# ProgrammateurFilPilote_1_1_1.net
KiCad netlist of a schematic drawn in EAGLE
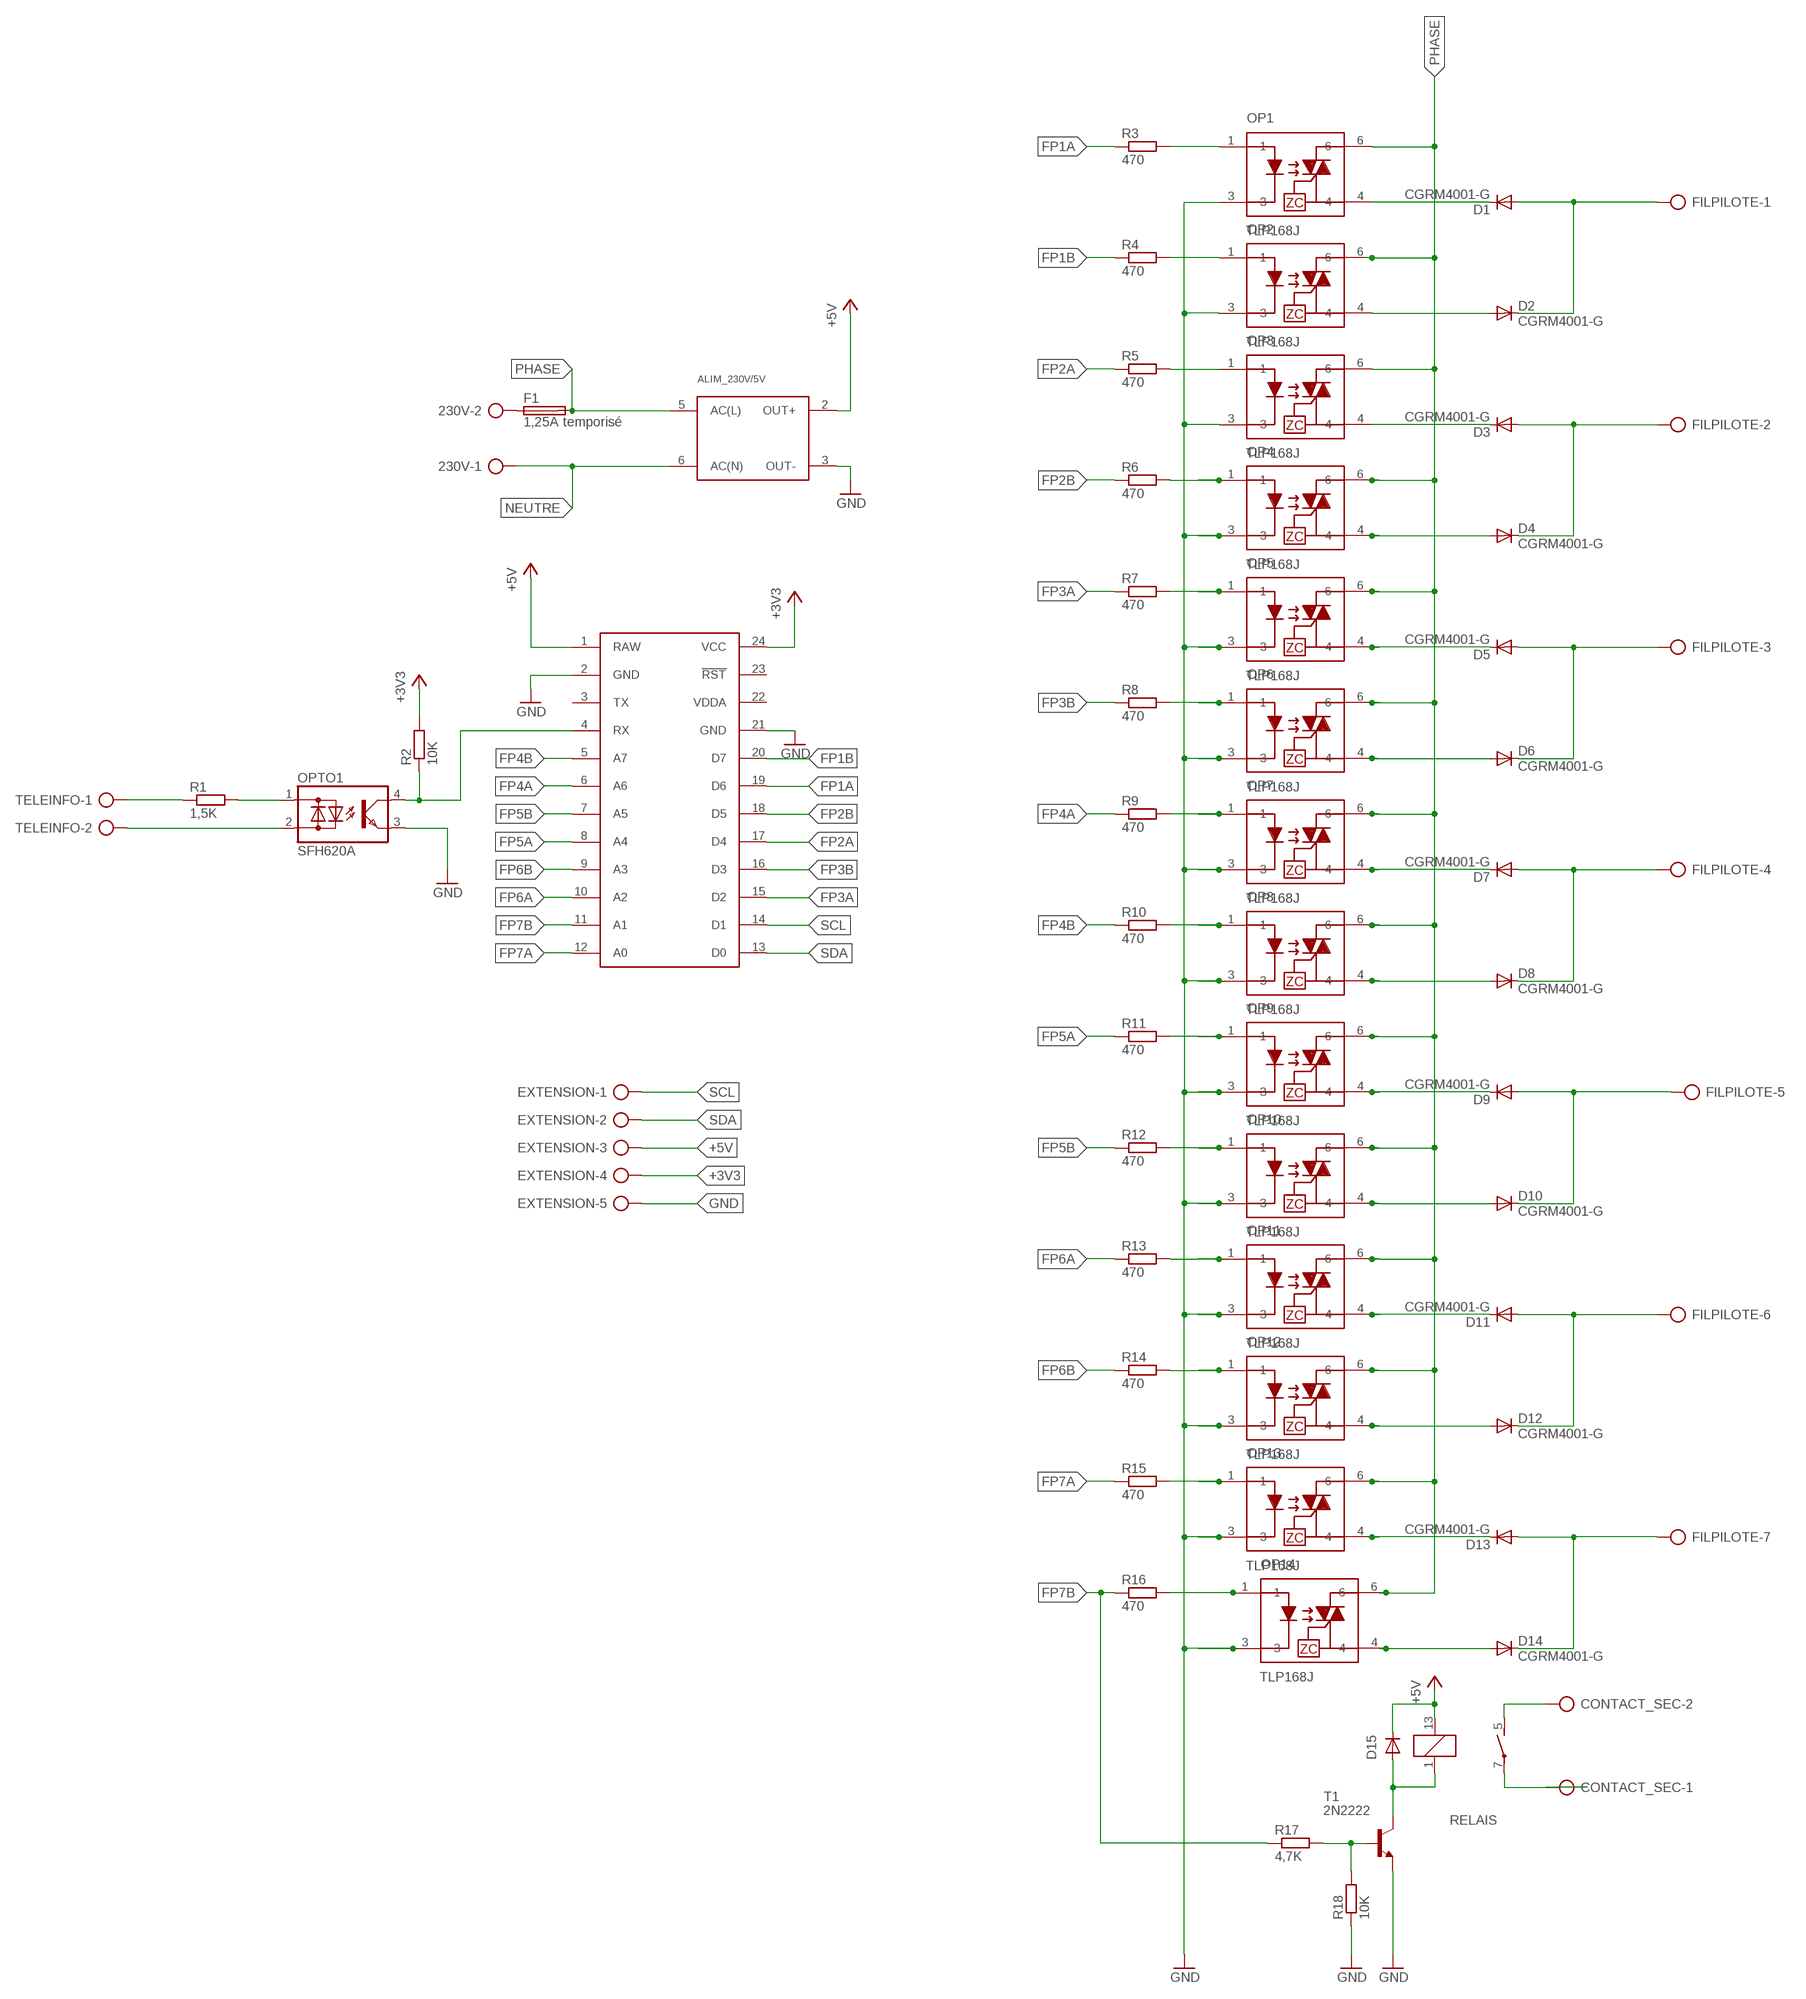
[diagram p0: schematic, sheet 1]

(export (version "E")
  (design (tool "Eeschema 10.0.6"))
  (components
    (comp (ref "230V")
      (value "AK500/2")
      (footprint "eagle-import:AK500_2")
      (libsource (lib "eagle-import") (part "AK500/2"))
    )
    (comp (ref "ALIM_230V/5V")
      (value "TMLM04-SINGLE")
      (footprint "eagle-import:TMLM04")
      (libsource (lib "eagle-import") (part "TMLM04-SINGLE"))
    )
    (comp (ref "CONTACT_SEC")
      (value "AK500/2")
      (footprint "eagle-import:AK500_2")
      (libsource (lib "eagle-import") (part "AK500/2"))
    )
    (comp (ref "D1")
      (value "CGRM4001-G")
      (footprint "eagle-import:SOD-123_MINI-SMA")
      (libsource (lib "eagle-import") (part "CGRM400-G1"))
    )
    (comp (ref "D2")
      (value "CGRM4001-G")
      (footprint "eagle-import:SOD-123_MINI-SMA")
      (libsource (lib "eagle-import") (part "CGRM400-G1"))
    )
    (comp (ref "D3")
      (value "CGRM4001-G")
      (footprint "eagle-import:SOD-123_MINI-SMA")
      (libsource (lib "eagle-import") (part "CGRM400-G1"))
    )
    (comp (ref "D4")
      (value "CGRM4001-G")
      (footprint "eagle-import:SOD-123_MINI-SMA")
      (libsource (lib "eagle-import") (part "CGRM400-G1"))
    )
    (comp (ref "D5")
      (value "CGRM4001-G")
      (footprint "eagle-import:SOD-123_MINI-SMA")
      (libsource (lib "eagle-import") (part "CGRM400-G1"))
    )
    (comp (ref "D6")
      (value "CGRM4001-G")
      (footprint "eagle-import:SOD-123_MINI-SMA")
      (libsource (lib "eagle-import") (part "CGRM400-G1"))
    )
    (comp (ref "D7")
      (value "CGRM4001-G")
      (footprint "eagle-import:SOD-123_MINI-SMA")
      (libsource (lib "eagle-import") (part "CGRM400-G1"))
    )
    (comp (ref "D8")
      (value "CGRM4001-G")
      (footprint "eagle-import:SOD-123_MINI-SMA")
      (libsource (lib "eagle-import") (part "CGRM400-G1"))
    )
    (comp (ref "D9")
      (value "CGRM4001-G")
      (footprint "eagle-import:SOD-123_MINI-SMA")
      (libsource (lib "eagle-import") (part "CGRM400-G1"))
    )
    (comp (ref "D10")
      (value "CGRM4001-G")
      (footprint "eagle-import:SOD-123_MINI-SMA")
      (libsource (lib "eagle-import") (part "CGRM400-G1"))
    )
    (comp (ref "D11")
      (value "CGRM4001-G")
      (footprint "eagle-import:SOD-123_MINI-SMA")
      (libsource (lib "eagle-import") (part "CGRM400-G1"))
    )
    (comp (ref "D12")
      (value "CGRM4001-G")
      (footprint "eagle-import:SOD-123_MINI-SMA")
      (libsource (lib "eagle-import") (part "CGRM400-G1"))
    )
    (comp (ref "D13")
      (value "CGRM4001-G")
      (footprint "eagle-import:SOD-123_MINI-SMA")
      (libsource (lib "eagle-import") (part "CGRM400-G1"))
    )
    (comp (ref "D14")
      (value "CGRM4001-G")
      (footprint "eagle-import:SOD-123_MINI-SMA")
      (libsource (lib "eagle-import") (part "CGRM400-G1"))
    )
    (comp (ref "D15")
      (value "CGRM4001-G")
      (footprint "eagle-import:SOD-123_MINI-SMA")
      (libsource (lib "eagle-import") (part "CGRM400-G1"))
    )
    (comp (ref "EXTENSION")
      (value "AK500/5")
      (footprint "eagle-import:AK500_5")
      (libsource (lib "eagle-import") (part "AK500/5"))
    )
    (comp (ref "F1")
      (value "1,25A temporisé")
      (footprint "eagle-import:TE5")
      (libsource (lib "eagle-import") (part "TE5"))
    )
    (comp (ref "FILPILOTE")
      (value "AK500/7")
      (footprint "eagle-import:AK500_7")
      (libsource (lib "eagle-import") (part "AK500/7"))
    )
    (comp (ref "OP1")
      (value "TLP168J")
      (footprint "eagle-import:MFSOP-4")
      (libsource (lib "eagle-import") (part "TLP168J"))
    )
    (comp (ref "OP2")
      (value "TLP168J")
      (footprint "eagle-import:MFSOP-4")
      (libsource (lib "eagle-import") (part "TLP168J"))
    )
    (comp (ref "OP3")
      (value "TLP168J")
      (footprint "eagle-import:MFSOP-4")
      (libsource (lib "eagle-import") (part "TLP168J"))
    )
    (comp (ref "OP4")
      (value "TLP168J")
      (footprint "eagle-import:MFSOP-4")
      (libsource (lib "eagle-import") (part "TLP168J"))
    )
    (comp (ref "OP5")
      (value "TLP168J")
      (footprint "eagle-import:MFSOP-4")
      (libsource (lib "eagle-import") (part "TLP168J"))
    )
    (comp (ref "OP6")
      (value "TLP168J")
      (footprint "eagle-import:MFSOP-4")
      (libsource (lib "eagle-import") (part "TLP168J"))
    )
    (comp (ref "OP7")
      (value "TLP168J")
      (footprint "eagle-import:MFSOP-4")
      (libsource (lib "eagle-import") (part "TLP168J"))
    )
    (comp (ref "OP8")
      (value "TLP168J")
      (footprint "eagle-import:MFSOP-4")
      (libsource (lib "eagle-import") (part "TLP168J"))
    )
    (comp (ref "OP9")
      (value "TLP168J")
      (footprint "eagle-import:MFSOP-4")
      (libsource (lib "eagle-import") (part "TLP168J"))
    )
    (comp (ref "OP10")
      (value "TLP168J")
      (footprint "eagle-import:MFSOP-4")
      (libsource (lib "eagle-import") (part "TLP168J"))
    )
    (comp (ref "OP11")
      (value "TLP168J")
      (footprint "eagle-import:MFSOP-4")
      (libsource (lib "eagle-import") (part "TLP168J"))
    )
    (comp (ref "OP12")
      (value "TLP168J")
      (footprint "eagle-import:MFSOP-4")
      (libsource (lib "eagle-import") (part "TLP168J"))
    )
    (comp (ref "OP13")
      (value "TLP168J")
      (footprint "eagle-import:MFSOP-4")
      (libsource (lib "eagle-import") (part "TLP168J"))
    )
    (comp (ref "OP14")
      (value "TLP168J")
      (footprint "eagle-import:MFSOP-4")
      (libsource (lib "eagle-import") (part "TLP168J"))
    )
    (comp (ref "OPTO1")
      (value "SFH620A")
      (footprint "eagle-import:DIL04")
      (fields (field (name "MPN") "SFH620A-2"))
      (libsource (lib "eagle-import") (part "SFH620A"))
    )
    (comp (ref "R1")
      (value "1,5K")
      (footprint "eagle-import:R1206")
      (libsource (lib "eagle-import") (part "R-EU_R1206"))
    )
    (comp (ref "R2")
      (value "10K")
      (footprint "eagle-import:R1206")
      (libsource (lib "eagle-import") (part "R-EU_R1206"))
    )
    (comp (ref "R3")
      (value "470")
      (footprint "eagle-import:R1206")
      (libsource (lib "eagle-import") (part "R-EU_R1206"))
    )
    (comp (ref "R4")
      (value "470")
      (footprint "eagle-import:R1206")
      (libsource (lib "eagle-import") (part "R-EU_R1206"))
    )
    (comp (ref "R5")
      (value "470")
      (footprint "eagle-import:R1206")
      (libsource (lib "eagle-import") (part "R-EU_R1206"))
    )
    (comp (ref "R6")
      (value "470")
      (footprint "eagle-import:R1206")
      (libsource (lib "eagle-import") (part "R-EU_R1206"))
    )
    (comp (ref "R7")
      (value "470")
      (footprint "eagle-import:R1206")
      (libsource (lib "eagle-import") (part "R-EU_R1206"))
    )
    (comp (ref "R8")
      (value "470")
      (footprint "eagle-import:R1206")
      (libsource (lib "eagle-import") (part "R-EU_R1206"))
    )
    (comp (ref "R9")
      (value "470")
      (footprint "eagle-import:R1206")
      (libsource (lib "eagle-import") (part "R-EU_R1206"))
    )
    (comp (ref "R10")
      (value "470")
      (footprint "eagle-import:R1206")
      (libsource (lib "eagle-import") (part "R-EU_R1206"))
    )
    (comp (ref "R11")
      (value "470")
      (footprint "eagle-import:R1206")
      (libsource (lib "eagle-import") (part "R-EU_R1206"))
    )
    (comp (ref "R12")
      (value "470")
      (footprint "eagle-import:R1206")
      (libsource (lib "eagle-import") (part "R-EU_R1206"))
    )
    (comp (ref "R13")
      (value "470")
      (footprint "eagle-import:R1206")
      (libsource (lib "eagle-import") (part "R-EU_R1206"))
    )
    (comp (ref "R14")
      (value "470")
      (footprint "eagle-import:R1206")
      (libsource (lib "eagle-import") (part "R-EU_R1206"))
    )
    (comp (ref "R15")
      (value "470")
      (footprint "eagle-import:R1206")
      (libsource (lib "eagle-import") (part "R-EU_R1206"))
    )
    (comp (ref "R16")
      (value "470")
      (footprint "eagle-import:R1206")
      (libsource (lib "eagle-import") (part "R-EU_R1206"))
    )
    (comp (ref "R17")
      (value "4,7K")
      (footprint "eagle-import:R1206")
      (libsource (lib "eagle-import") (part "R-EU_R1206"))
    )
    (comp (ref "R18")
      (value "10K")
      (footprint "eagle-import:R1206")
      (libsource (lib "eagle-import") (part "R-EU_R1206"))
    )
    (comp (ref "RELAIS")
      (value "Relais G6D")
      (footprint "eagle-import:G6D")
      (libsource (lib "eagle-import") (part "G6D?-1A-ASI12VDC"))
    )
    (comp (ref "SPARKCORE")
      (value "SPARK_CORECORE")
      (footprint "eagle-import:SPARK_CORE")
      (libsource (lib "eagle-import") (part "SPARK_CORECORE"))
    )
    (comp (ref "T1")
      (value "2N2222")
      (footprint "eagle-import:TO92-EBC")
      (libsource (lib "eagle-import") (part "-NPN-TO92-EBC2N2222"))
    )
    (comp (ref "TELEINFO")
      (value "AK500/2")
      (footprint "eagle-import:AK500_2")
      (libsource (lib "eagle-import") (part "AK500/2"))
    )
  )
  (nets
    (net (code "1") (name "+3V3") (class "Default")
      (node (ref "EXTENSION") (pin "4") (pinfunction "KL_4") (pintype "passive"))
      (node (ref "R2") (pin "2") (pinfunction "2_2") (pintype "passive"))
      (node (ref "SPARKCORE") (pin "24") (pinfunction "VCC_24") (pintype "power_in"))
    )
    (net (code "2") (name "+5V") (class "Default")
      (node (ref "ALIM_230V/5V") (pin "2") (pinfunction "OUT+_2") (pintype "passive"))
      (node (ref "D15") (pin "C") (pinfunction "C_C") (pintype "passive"))
      (node (ref "EXTENSION") (pin "3") (pinfunction "KL_3") (pintype "passive"))
      (node (ref "RELAIS") (pin "13") (pinfunction "2_13") (pintype "passive"))
      (node (ref "SPARKCORE") (pin "1") (pinfunction "RAW_1") (pintype "power_in"))
    )
    (net (code "3") (name "/VDDA") (class "Default")
      (node (ref "SPARKCORE") (pin "22") (pinfunction "VDDA_22") (pintype "power_in"))
    )
    (net (code "4") (name "FP1A") (class "Default")
      (node (ref "R3") (pin "1") (pinfunction "1_1") (pintype "passive"))
      (node (ref "SPARKCORE") (pin "19") (pinfunction "D6_19") (pintype "bidirectional"))
    )
    (net (code "5") (name "FP1B") (class "Default")
      (node (ref "R4") (pin "1") (pinfunction "1_1") (pintype "passive"))
      (node (ref "SPARKCORE") (pin "20") (pinfunction "D7_20") (pintype "bidirectional"))
    )
    (net (code "6") (name "FP2A") (class "Default")
      (node (ref "R5") (pin "1") (pinfunction "1_1") (pintype "passive"))
      (node (ref "SPARKCORE") (pin "17") (pinfunction "D4_17") (pintype "bidirectional"))
    )
    (net (code "7") (name "FP2B") (class "Default")
      (node (ref "R6") (pin "1") (pinfunction "1_1") (pintype "passive"))
      (node (ref "SPARKCORE") (pin "18") (pinfunction "D5_18") (pintype "bidirectional"))
    )
    (net (code "8") (name "FP3A") (class "Default")
      (node (ref "R7") (pin "1") (pinfunction "1_1") (pintype "passive"))
      (node (ref "SPARKCORE") (pin "15") (pinfunction "D2_15") (pintype "bidirectional"))
    )
    (net (code "9") (name "FP3B") (class "Default")
      (node (ref "R8") (pin "1") (pinfunction "1_1") (pintype "passive"))
      (node (ref "SPARKCORE") (pin "16") (pinfunction "D3_16") (pintype "bidirectional"))
    )
    (net (code "10") (name "FP4A") (class "Default")
      (node (ref "R9") (pin "1") (pinfunction "1_1") (pintype "passive"))
      (node (ref "SPARKCORE") (pin "6") (pinfunction "A6_6") (pintype "bidirectional"))
    )
    (net (code "11") (name "FP4B") (class "Default")
      (node (ref "R10") (pin "1") (pinfunction "1_1") (pintype "passive"))
      (node (ref "SPARKCORE") (pin "5") (pinfunction "A7_5") (pintype "bidirectional"))
    )
    (net (code "12") (name "FP5A") (class "Default")
      (node (ref "R11") (pin "1") (pinfunction "1_1") (pintype "passive"))
      (node (ref "SPARKCORE") (pin "8") (pinfunction "A4_8") (pintype "bidirectional"))
    )
    (net (code "13") (name "FP5B") (class "Default")
      (node (ref "R12") (pin "1") (pinfunction "1_1") (pintype "passive"))
      (node (ref "SPARKCORE") (pin "7") (pinfunction "A5_7") (pintype "bidirectional"))
    )
    (net (code "14") (name "FP6A") (class "Default")
      (node (ref "R13") (pin "1") (pinfunction "1_1") (pintype "passive"))
      (node (ref "SPARKCORE") (pin "10") (pinfunction "A2_10") (pintype "bidirectional"))
    )
    (net (code "15") (name "FP6B") (class "Default")
      (node (ref "R14") (pin "1") (pinfunction "1_1") (pintype "passive"))
      (node (ref "SPARKCORE") (pin "9") (pinfunction "A3_9") (pintype "bidirectional"))
    )
    (net (code "16") (name "FP7A") (class "Default")
      (node (ref "R15") (pin "1") (pinfunction "1_1") (pintype "passive"))
      (node (ref "SPARKCORE") (pin "12") (pinfunction "A0_12") (pintype "bidirectional"))
    )
    (net (code "17") (name "FP7B") (class "Default")
      (node (ref "R16") (pin "1") (pinfunction "1_1") (pintype "passive"))
      (node (ref "R17") (pin "1") (pinfunction "1_1") (pintype "passive"))
      (node (ref "SPARKCORE") (pin "11") (pinfunction "A1_11") (pintype "bidirectional"))
    )
    (net (code "18") (name "GND") (class "Default")
      (node (ref "ALIM_230V/5V") (pin "3") (pinfunction "OUT-_3") (pintype "passive"))
      (node (ref "EXTENSION") (pin "5") (pinfunction "KL_5") (pintype "passive"))
      (node (ref "OP1") (pin "3") (pinfunction "3_3") (pintype "bidirectional"))
      (node (ref "OP10") (pin "3") (pinfunction "3_3") (pintype "bidirectional"))
      (node (ref "OP11") (pin "3") (pinfunction "3_3") (pintype "bidirectional"))
      (node (ref "OP12") (pin "3") (pinfunction "3_3") (pintype "bidirectional"))
      (node (ref "OP13") (pin "3") (pinfunction "3_3") (pintype "bidirectional"))
      (node (ref "OP14") (pin "3") (pinfunction "3_3") (pintype "bidirectional"))
      (node (ref "OP2") (pin "3") (pinfunction "3_3") (pintype "bidirectional"))
      (node (ref "OP3") (pin "3") (pinfunction "3_3") (pintype "bidirectional"))
      (node (ref "OP4") (pin "3") (pinfunction "3_3") (pintype "bidirectional"))
      (node (ref "OP5") (pin "3") (pinfunction "3_3") (pintype "bidirectional"))
      (node (ref "OP6") (pin "3") (pinfunction "3_3") (pintype "bidirectional"))
      (node (ref "OP7") (pin "3") (pinfunction "3_3") (pintype "bidirectional"))
      (node (ref "OP8") (pin "3") (pinfunction "3_3") (pintype "bidirectional"))
      (node (ref "OP9") (pin "3") (pinfunction "3_3") (pintype "bidirectional"))
      (node (ref "OPTO1") (pin "3") (pinfunction "E_3") (pintype "passive"))
      (node (ref "R18") (pin "1") (pinfunction "1_1") (pintype "passive"))
      (node (ref "SPARKCORE") (pin "2") (pinfunction "GND_2") (pintype "power_in"))
      (node (ref "SPARKCORE") (pin "21") (pinfunction "GND_21") (pintype "power_in"))
      (node (ref "T1") (pin "E") (pinfunction "E_E") (pintype "passive"))
    )
    (net (code "19") (name "NEUTRE") (class "Default")
      (node (ref "230V") (pin "1") (pinfunction "KL_1") (pintype "passive"))
      (node (ref "ALIM_230V/5V") (pin "6") (pinfunction "AC(N)_6") (pintype "input"))
    )
    (net (code "20") (name "Net-(230VB-KL)") (class "Default")
      (node (ref "230V") (pin "2") (pinfunction "KL_2") (pintype "passive"))
      (node (ref "F1") (pin "1") (pinfunction "1_1") (pintype "passive"))
    )
    (net (code "21") (name "Net-(CONTACT_SECA-KL)") (class "Default")
      (node (ref "CONTACT_SEC") (pin "1") (pinfunction "KL_1") (pintype "passive"))
      (node (ref "RELAIS") (pin "7") (pinfunction "P_7") (pintype "passive"))
    )
    (net (code "22") (name "Net-(CONTACT_SECB-KL)") (class "Default")
      (node (ref "CONTACT_SEC") (pin "2") (pinfunction "KL_2") (pintype "passive"))
      (node (ref "RELAIS") (pin "5") (pinfunction "S_5") (pintype "passive"))
    )
    (net (code "23") (name "Net-(D1-PadC)") (class "Default")
      (node (ref "D1") (pin "C") (pinfunction "C_C") (pintype "passive"))
      (node (ref "OP1") (pin "4") (pinfunction "4_4") (pintype "bidirectional"))
    )
    (net (code "24") (name "Net-(D2-PadA)") (class "Default")
      (node (ref "D2") (pin "A") (pinfunction "A_A") (pintype "passive"))
      (node (ref "OP2") (pin "4") (pinfunction "4_4") (pintype "bidirectional"))
    )
    (net (code "25") (name "Net-(D3-PadC)") (class "Default")
      (node (ref "D3") (pin "C") (pinfunction "C_C") (pintype "passive"))
      (node (ref "OP3") (pin "4") (pinfunction "4_4") (pintype "bidirectional"))
    )
    (net (code "26") (name "Net-(D4-PadA)") (class "Default")
      (node (ref "D4") (pin "A") (pinfunction "A_A") (pintype "passive"))
      (node (ref "OP4") (pin "4") (pinfunction "4_4") (pintype "bidirectional"))
    )
    (net (code "27") (name "Net-(D5-PadC)") (class "Default")
      (node (ref "D5") (pin "C") (pinfunction "C_C") (pintype "passive"))
      (node (ref "OP5") (pin "4") (pinfunction "4_4") (pintype "bidirectional"))
    )
    (net (code "28") (name "Net-(D6-PadA)") (class "Default")
      (node (ref "D6") (pin "A") (pinfunction "A_A") (pintype "passive"))
      (node (ref "OP6") (pin "4") (pinfunction "4_4") (pintype "bidirectional"))
    )
    (net (code "29") (name "Net-(D7-PadC)") (class "Default")
      (node (ref "D7") (pin "C") (pinfunction "C_C") (pintype "passive"))
      (node (ref "OP7") (pin "4") (pinfunction "4_4") (pintype "bidirectional"))
    )
    (net (code "30") (name "Net-(D8-PadA)") (class "Default")
      (node (ref "D8") (pin "A") (pinfunction "A_A") (pintype "passive"))
      (node (ref "OP8") (pin "4") (pinfunction "4_4") (pintype "bidirectional"))
    )
    (net (code "31") (name "Net-(D9-PadC)") (class "Default")
      (node (ref "D9") (pin "C") (pinfunction "C_C") (pintype "passive"))
      (node (ref "OP9") (pin "4") (pinfunction "4_4") (pintype "bidirectional"))
    )
    (net (code "32") (name "Net-(D10-PadA)") (class "Default")
      (node (ref "D10") (pin "A") (pinfunction "A_A") (pintype "passive"))
      (node (ref "OP10") (pin "4") (pinfunction "4_4") (pintype "bidirectional"))
    )
    (net (code "33") (name "Net-(D11-PadC)") (class "Default")
      (node (ref "D11") (pin "C") (pinfunction "C_C") (pintype "passive"))
      (node (ref "OP11") (pin "4") (pinfunction "4_4") (pintype "bidirectional"))
    )
    (net (code "34") (name "Net-(D12-PadA)") (class "Default")
      (node (ref "D12") (pin "A") (pinfunction "A_A") (pintype "passive"))
      (node (ref "OP12") (pin "4") (pinfunction "4_4") (pintype "bidirectional"))
    )
    (net (code "35") (name "Net-(D13-PadC)") (class "Default")
      (node (ref "D13") (pin "C") (pinfunction "C_C") (pintype "passive"))
      (node (ref "OP13") (pin "4") (pinfunction "4_4") (pintype "bidirectional"))
    )
    (net (code "36") (name "Net-(D14-PadA)") (class "Default")
      (node (ref "D14") (pin "A") (pinfunction "A_A") (pintype "passive"))
      (node (ref "OP14") (pin "4") (pinfunction "4_4") (pintype "bidirectional"))
    )
    (net (code "37") (name "Net-(D15-PadA)") (class "Default")
      (node (ref "D15") (pin "A") (pinfunction "A_A") (pintype "passive"))
      (node (ref "RELAIS") (pin "1") (pinfunction "1_1") (pintype "passive"))
      (node (ref "T1") (pin "C") (pinfunction "C_C") (pintype "passive"))
    )
    (net (code "38") (name "Net-(FILPILOTEA-KL)") (class "Default")
      (node (ref "D1") (pin "A") (pinfunction "A_A") (pintype "passive"))
      (node (ref "D2") (pin "C") (pinfunction "C_C") (pintype "passive"))
      (node (ref "FILPILOTE") (pin "1") (pinfunction "KL_1") (pintype "passive"))
    )
    (net (code "39") (name "Net-(FILPILOTEB-KL)") (class "Default")
      (node (ref "D3") (pin "A") (pinfunction "A_A") (pintype "passive"))
      (node (ref "D4") (pin "C") (pinfunction "C_C") (pintype "passive"))
      (node (ref "FILPILOTE") (pin "2") (pinfunction "KL_2") (pintype "passive"))
    )
    (net (code "40") (name "Net-(FILPILOTEC-KL)") (class "Default")
      (node (ref "D5") (pin "A") (pinfunction "A_A") (pintype "passive"))
      (node (ref "D6") (pin "C") (pinfunction "C_C") (pintype "passive"))
      (node (ref "FILPILOTE") (pin "3") (pinfunction "KL_3") (pintype "passive"))
    )
    (net (code "41") (name "Net-(FILPILOTED-KL)") (class "Default")
      (node (ref "D7") (pin "A") (pinfunction "A_A") (pintype "passive"))
      (node (ref "D8") (pin "C") (pinfunction "C_C") (pintype "passive"))
      (node (ref "FILPILOTE") (pin "4") (pinfunction "KL_4") (pintype "passive"))
    )
    (net (code "42") (name "Net-(FILPILOTEE-KL)") (class "Default")
      (node (ref "D10") (pin "C") (pinfunction "C_C") (pintype "passive"))
      (node (ref "D9") (pin "A") (pinfunction "A_A") (pintype "passive"))
      (node (ref "FILPILOTE") (pin "5") (pinfunction "KL_5") (pintype "passive"))
    )
    (net (code "43") (name "Net-(FILPILOTEF-KL)") (class "Default")
      (node (ref "D11") (pin "A") (pinfunction "A_A") (pintype "passive"))
      (node (ref "D12") (pin "C") (pinfunction "C_C") (pintype "passive"))
      (node (ref "FILPILOTE") (pin "6") (pinfunction "KL_6") (pintype "passive"))
    )
    (net (code "44") (name "Net-(FILPILOTEG-KL)") (class "Default")
      (node (ref "D13") (pin "A") (pinfunction "A_A") (pintype "passive"))
      (node (ref "D14") (pin "C") (pinfunction "C_C") (pintype "passive"))
      (node (ref "FILPILOTE") (pin "7") (pinfunction "KL_7") (pintype "passive"))
    )
    (net (code "45") (name "Net-(OP1-Pad1)") (class "Default")
      (node (ref "OP1") (pin "1") (pinfunction "1_1") (pintype "bidirectional"))
      (node (ref "R3") (pin "2") (pinfunction "2_2") (pintype "passive"))
    )
    (net (code "46") (name "Net-(OP2-Pad1)") (class "Default")
      (node (ref "OP2") (pin "1") (pinfunction "1_1") (pintype "bidirectional"))
      (node (ref "R4") (pin "2") (pinfunction "2_2") (pintype "passive"))
    )
    (net (code "47") (name "Net-(OP3-Pad1)") (class "Default")
      (node (ref "OP3") (pin "1") (pinfunction "1_1") (pintype "bidirectional"))
      (node (ref "R5") (pin "2") (pinfunction "2_2") (pintype "passive"))
    )
    (net (code "48") (name "Net-(OP4-Pad1)") (class "Default")
      (node (ref "OP4") (pin "1") (pinfunction "1_1") (pintype "bidirectional"))
      (node (ref "R6") (pin "2") (pinfunction "2_2") (pintype "passive"))
    )
    (net (code "49") (name "Net-(OP5-Pad1)") (class "Default")
      (node (ref "OP5") (pin "1") (pinfunction "1_1") (pintype "bidirectional"))
      (node (ref "R7") (pin "2") (pinfunction "2_2") (pintype "passive"))
    )
    (net (code "50") (name "Net-(OP6-Pad1)") (class "Default")
      (node (ref "OP6") (pin "1") (pinfunction "1_1") (pintype "bidirectional"))
      (node (ref "R8") (pin "2") (pinfunction "2_2") (pintype "passive"))
    )
    (net (code "51") (name "Net-(OP7-Pad1)") (class "Default")
      (node (ref "OP7") (pin "1") (pinfunction "1_1") (pintype "bidirectional"))
      (node (ref "R9") (pin "2") (pinfunction "2_2") (pintype "passive"))
    )
    (net (code "52") (name "Net-(OP8-Pad1)") (class "Default")
      (node (ref "OP8") (pin "1") (pinfunction "1_1") (pintype "bidirectional"))
      (node (ref "R10") (pin "2") (pinfunction "2_2") (pintype "passive"))
    )
    (net (code "53") (name "Net-(OP9-Pad1)") (class "Default")
      (node (ref "OP9") (pin "1") (pinfunction "1_1") (pintype "bidirectional"))
      (node (ref "R11") (pin "2") (pinfunction "2_2") (pintype "passive"))
    )
    (net (code "54") (name "Net-(OP10-Pad1)") (class "Default")
      (node (ref "OP10") (pin "1") (pinfunction "1_1") (pintype "bidirectional"))
      (node (ref "R12") (pin "2") (pinfunction "2_2") (pintype "passive"))
    )
    (net (code "55") (name "Net-(OP11-Pad1)") (class "Default")
      (node (ref "OP11") (pin "1") (pinfunction "1_1") (pintype "bidirectional"))
      (node (ref "R13") (pin "2") (pinfunction "2_2") (pintype "passive"))
    )
    (net (code "56") (name "Net-(OP12-Pad1)") (class "Default")
      (node (ref "OP12") (pin "1") (pinfunction "1_1") (pintype "bidirectional"))
      (node (ref "R14") (pin "2") (pinfunction "2_2") (pintype "passive"))
    )
    (net (code "57") (name "Net-(OP13-Pad1)") (class "Default")
      (node (ref "OP13") (pin "1") (pinfunction "1_1") (pintype "bidirectional"))
      (node (ref "R15") (pin "2") (pinfunction "2_2") (pintype "passive"))
    )
    (net (code "58") (name "Net-(OP14-Pad1)") (class "Default")
      (node (ref "OP14") (pin "1") (pinfunction "1_1") (pintype "bidirectional"))
      (node (ref "R16") (pin "2") (pinfunction "2_2") (pintype "passive"))
    )
    (net (code "59") (name "Net-(OPTO1-AC1)") (class "Default")
      (node (ref "OPTO1") (pin "1") (pinfunction "AC1_1") (pintype "passive"))
      (node (ref "R1") (pin "2") (pinfunction "2_2") (pintype "passive"))
    )
    (net (code "60") (name "Net-(OPTO1-AC2)") (class "Default")
      (node (ref "OPTO1") (pin "2") (pinfunction "AC2_2") (pintype "passive"))
      (node (ref "TELEINFO") (pin "2") (pinfunction "KL_2") (pintype "passive"))
    )
    (net (code "61") (name "Net-(OPTO1-C)") (class "Default")
      (node (ref "OPTO1") (pin "4") (pinfunction "C_4") (pintype "passive"))
      (node (ref "R2") (pin "1") (pinfunction "1_1") (pintype "passive"))
      (node (ref "SPARKCORE") (pin "4") (pinfunction "RX_4") (pintype "bidirectional"))
    )
    (net (code "62") (name "Net-(R17-Pad2)") (class "Default")
      (node (ref "R17") (pin "2") (pinfunction "2_2") (pintype "passive"))
      (node (ref "R18") (pin "2") (pinfunction "2_2") (pintype "passive"))
      (node (ref "T1") (pin "B") (pinfunction "B_B") (pintype "passive"))
    )
    (net (code "63") (name "Net-(TELEINFOA-KL)") (class "Default")
      (node (ref "R1") (pin "1") (pinfunction "1_1") (pintype "passive"))
      (node (ref "TELEINFO") (pin "1") (pinfunction "KL_1") (pintype "passive"))
    )
    (net (code "64") (name "PHASE") (class "Default")
      (node (ref "ALIM_230V/5V") (pin "5") (pinfunction "AC(L)_5") (pintype "input"))
      (node (ref "F1") (pin "2") (pinfunction "2_2") (pintype "passive"))
      (node (ref "OP1") (pin "6") (pinfunction "6_6") (pintype "bidirectional"))
      (node (ref "OP10") (pin "6") (pinfunction "6_6") (pintype "bidirectional"))
      (node (ref "OP11") (pin "6") (pinfunction "6_6") (pintype "bidirectional"))
      (node (ref "OP12") (pin "6") (pinfunction "6_6") (pintype "bidirectional"))
      (node (ref "OP13") (pin "6") (pinfunction "6_6") (pintype "bidirectional"))
      (node (ref "OP14") (pin "6") (pinfunction "6_6") (pintype "bidirectional"))
      (node (ref "OP2") (pin "6") (pinfunction "6_6") (pintype "bidirectional"))
      (node (ref "OP3") (pin "6") (pinfunction "6_6") (pintype "bidirectional"))
      (node (ref "OP4") (pin "6") (pinfunction "6_6") (pintype "bidirectional"))
      (node (ref "OP5") (pin "6") (pinfunction "6_6") (pintype "bidirectional"))
      (node (ref "OP6") (pin "6") (pinfunction "6_6") (pintype "bidirectional"))
      (node (ref "OP7") (pin "6") (pinfunction "6_6") (pintype "bidirectional"))
      (node (ref "OP8") (pin "6") (pinfunction "6_6") (pintype "bidirectional"))
      (node (ref "OP9") (pin "6") (pinfunction "6_6") (pintype "bidirectional"))
    )
    (net (code "65") (name "SCL") (class "Default")
      (node (ref "EXTENSION") (pin "1") (pinfunction "KL_1") (pintype "passive"))
      (node (ref "SPARKCORE") (pin "14") (pinfunction "D1_14") (pintype "bidirectional"))
    )
    (net (code "66") (name "SDA") (class "Default")
      (node (ref "EXTENSION") (pin "2") (pinfunction "KL_2") (pintype "passive"))
      (node (ref "SPARKCORE") (pin "13") (pinfunction "D0_13") (pintype "bidirectional"))
    )
    (net (code "67") (name "unconnected-(SPARKCORE-TX-Pad3)") (class "Default")
      (node (ref "SPARKCORE") (pin "3") (pinfunction "TX_3") (pintype "bidirectional"))
    )
    (net (code "68") (name "unconnected-(SPARKCORE-~{RST}-Pad23)") (class "Default")
      (node (ref "SPARKCORE") (pin "23") (pinfunction "~{RST}_23") (pintype "bidirectional"))
    )
  )
)
